# LCD_Player_V1_1.net
KiCad netlist of a schematic drawn in Altium Designer
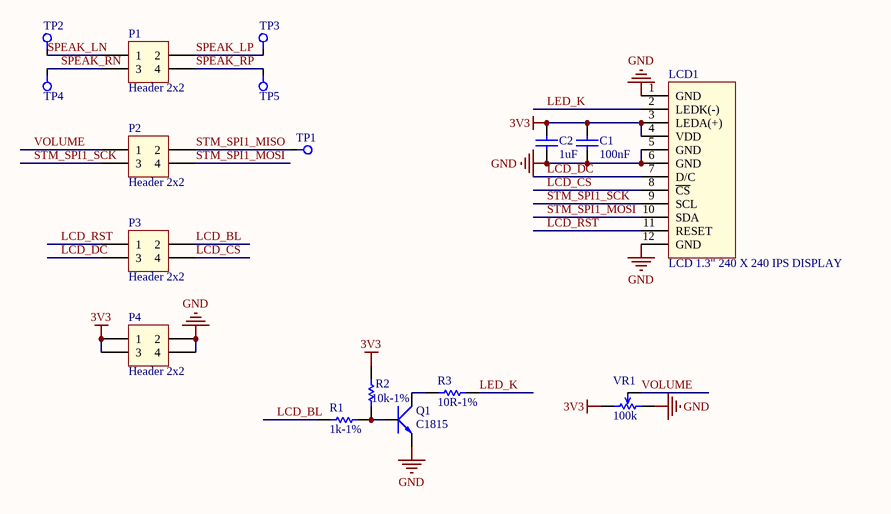
[diagram p0: LCD_Player_V1.1.SchDoc]

(export (version "E")
  (design (tool "Eeschema 10.0.6"))
  (components
    (comp (ref "C1")
      (value "100nF")
      (footprint "Cap 0603")
      (description "Cap SMD")
      (libsource (lib "duchuylee") (part "Cap"))
    )
    (comp (ref "C2")
      (value "1uF")
      (footprint "Cap 0603")
      (description "Cap SMD")
      (libsource (lib "duchuylee") (part "Cap"))
    )
    (comp (ref "LCD1")
      (value "LCD 1.3\" 240 X 240 IPS DISPLAY")
      (footprint "LCD 1.3inch IPS HD")
      (libsource (lib "duchuylee") (part "LCD 1.3{dblquote} 240 X 240 IPS DISPLAY"))
    )
    (comp (ref "P1")
      (value "Header 2x2")
      (footprint "Header 2mm 2x2")
      (libsource (lib "duchuylee") (part "Header 2x2"))
    )
    (comp (ref "P2")
      (value "Header 2x2")
      (footprint "Header 2mm 2x2")
      (libsource (lib "duchuylee") (part "Header 2x2"))
    )
    (comp (ref "P3")
      (value "Header 2x2")
      (footprint "Header 2mm 2x2")
      (libsource (lib "duchuylee") (part "Header 2x2"))
    )
    (comp (ref "P4")
      (value "Header 2x2")
      (footprint "Header 2mm 2x2")
      (libsource (lib "duchuylee") (part "Header 2x2"))
    )
    (comp (ref "Q1")
      (value "C1815")
      (footprint "SOT23B")
      (description "NPN 600mW, ECB")
      (libsource (lib "syhaunguyen") (part "C1815"))
    )
    (comp (ref "R1")
      (value "1k-1%")
      (footprint "Res 0603")
      (description "Res SMD")
      (libsource (lib "duchuylee") (part "Res"))
    )
    (comp (ref "R2")
      (value "10k-1%")
      (footprint "Res 0603")
      (description "Res SMD")
      (libsource (lib "duchuylee") (part "Res"))
    )
    (comp (ref "R3")
      (value "10R-1%")
      (footprint "Res 0603")
      (description "Res SMD")
      (libsource (lib "duchuylee") (part "Res"))
    )
    (comp (ref "TP1") (value "TP") (footprint "duchuylee:TP") (libsource (lib "duchuylee") (part "TP")))
    (comp (ref "TP2") (value "TP") (footprint "duchuylee:TP") (libsource (lib "duchuylee") (part "TP")))
    (comp (ref "TP3") (value "TP") (footprint "duchuylee:TP") (libsource (lib "duchuylee") (part "TP")))
    (comp (ref "TP4") (value "TP") (footprint "duchuylee:TP") (libsource (lib "duchuylee") (part "TP")))
    (comp (ref "TP5") (value "TP") (footprint "duchuylee:TP") (libsource (lib "duchuylee") (part "TP")))
    (comp (ref "VR1")
      (value "100k")
      (footprint "Adjust Resistor Wheel")
      (description "Adjust Resistor")
      (libsource (lib "duchuylee") (part "Res Adjust"))
    )
  )
  (nets
    (net (code "1") (name "/LCD_BL") (class "Default")
      (node (ref "P3") (pin "2") (pinfunction "2_2") (pintype "passive"))
      (node (ref "R1") (pin "1") (pinfunction "1_1") (pintype "passive"))
    )
    (net (code "2") (name "/LCD_CS") (class "Default")
      (node (ref "LCD1") (pin "8") (pinfunction "~{CS}_8") (pintype "passive"))
      (node (ref "P3") (pin "4") (pinfunction "4_4") (pintype "passive"))
    )
    (net (code "3") (name "/LCD_DC") (class "Default")
      (node (ref "LCD1") (pin "7") (pinfunction "D/C_7") (pintype "passive"))
      (node (ref "P3") (pin "3") (pinfunction "3_3") (pintype "passive"))
    )
    (net (code "4") (name "/LCD_RST") (class "Default")
      (node (ref "LCD1") (pin "11") (pinfunction "RESET_11") (pintype "passive"))
      (node (ref "P3") (pin "1") (pinfunction "1_1") (pintype "passive"))
    )
    (net (code "5") (name "/LED_K") (class "Default")
      (node (ref "LCD1") (pin "2") (pinfunction "LEDK(-)_2") (pintype "passive"))
      (node (ref "R3") (pin "1") (pinfunction "1_1") (pintype "passive"))
    )
    (net (code "6") (name "/SPEAK_LN") (class "Default")
      (node (ref "P1") (pin "1") (pinfunction "1_1") (pintype "passive"))
      (node (ref "TP2") (pin "1") (pinfunction "1_1") (pintype "passive"))
    )
    (net (code "7") (name "/SPEAK_LP") (class "Default")
      (node (ref "P1") (pin "2") (pinfunction "2_2") (pintype "passive"))
      (node (ref "TP3") (pin "1") (pinfunction "1_1") (pintype "passive"))
    )
    (net (code "8") (name "/SPEAK_RN") (class "Default")
      (node (ref "P1") (pin "3") (pinfunction "3_3") (pintype "passive"))
      (node (ref "TP4") (pin "1") (pinfunction "1_1") (pintype "passive"))
    )
    (net (code "9") (name "/SPEAK_RP") (class "Default")
      (node (ref "P1") (pin "4") (pinfunction "4_4") (pintype "passive"))
      (node (ref "TP5") (pin "1") (pinfunction "1_1") (pintype "passive"))
    )
    (net (code "10") (name "/STM_SPI1_MISO") (class "Default")
      (node (ref "P2") (pin "2") (pinfunction "2_2") (pintype "passive"))
      (node (ref "TP1") (pin "1") (pinfunction "1_1") (pintype "passive"))
    )
    (net (code "11") (name "/STM_SPI1_MOSI") (class "Default")
      (node (ref "LCD1") (pin "10") (pinfunction "SDA_10") (pintype "passive"))
      (node (ref "P2") (pin "4") (pinfunction "4_4") (pintype "passive"))
    )
    (net (code "12") (name "/STM_SPI1_SCK") (class "Default")
      (node (ref "LCD1") (pin "9") (pinfunction "SCL_9") (pintype "passive"))
      (node (ref "P2") (pin "3") (pinfunction "3_3") (pintype "passive"))
    )
    (net (code "13") (name "/VOLUME") (class "Default")
      (node (ref "P2") (pin "1") (pinfunction "1_1") (pintype "passive"))
      (node (ref "VR1") (pin "2") (pinfunction "2_2") (pintype "passive"))
    )
    (net (code "14") (name "3V3") (class "Default")
      (node (ref "C1") (pin "1") (pinfunction "1_1") (pintype "passive"))
      (node (ref "C2") (pin "1") (pinfunction "1_1") (pintype "passive"))
      (node (ref "LCD1") (pin "3") (pinfunction "LEDA(+)_3") (pintype "passive"))
      (node (ref "LCD1") (pin "4") (pinfunction "VDD_4") (pintype "passive"))
      (node (ref "P4") (pin "1") (pinfunction "1_1") (pintype "passive"))
      (node (ref "P4") (pin "3") (pinfunction "3_3") (pintype "passive"))
      (node (ref "R2") (pin "2") (pinfunction "2_2") (pintype "passive"))
      (node (ref "VR1") (pin "1") (pinfunction "1_1") (pintype "passive"))
    )
    (net (code "15") (name "GND") (class "Default")
      (node (ref "C1") (pin "2") (pinfunction "2_2") (pintype "passive"))
      (node (ref "C2") (pin "2") (pinfunction "2_2") (pintype "passive"))
      (node (ref "LCD1") (pin "1") (pinfunction "GND_1") (pintype "passive"))
      (node (ref "LCD1") (pin "12") (pinfunction "GND_12") (pintype "passive"))
      (node (ref "LCD1") (pin "5") (pinfunction "GND_5") (pintype "passive"))
      (node (ref "LCD1") (pin "6") (pinfunction "GND_6") (pintype "passive"))
      (node (ref "P4") (pin "2") (pinfunction "2_2") (pintype "passive"))
      (node (ref "P4") (pin "4") (pinfunction "4_4") (pintype "passive"))
      (node (ref "Q1") (pin "1") (pinfunction "E_1") (pintype "passive"))
      (node (ref "VR1") (pin "3") (pinfunction "3_3") (pintype "passive"))
    )
    (net (code "16") (name "Net-(Q1-B)") (class "Default")
      (node (ref "Q1") (pin "3") (pinfunction "B_3") (pintype "passive"))
      (node (ref "R1") (pin "2") (pinfunction "2_2") (pintype "passive"))
      (node (ref "R2") (pin "1") (pinfunction "1_1") (pintype "passive"))
    )
    (net (code "17") (name "Net-(Q1-C)") (class "Default")
      (node (ref "Q1") (pin "2") (pinfunction "C_2") (pintype "passive"))
      (node (ref "R3") (pin "2") (pinfunction "2_2") (pintype "passive"))
    )
  )
)
